# Industrial-Controller_Fan.net
KiCad netlist of a schematic drawn in Altium Designer
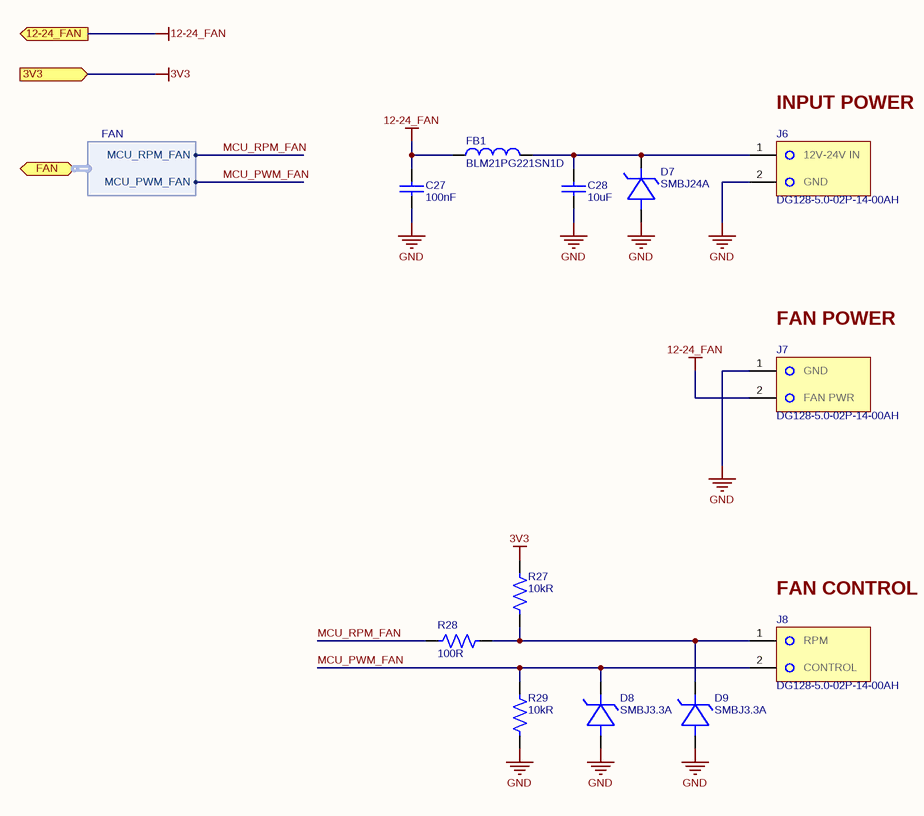
[diagram p0: Industrial-Controller_Fan.SchDoc]

(export (version "E")
  (design (tool "Eeschema 10.0.6"))
  (components
    (comp (ref "C27")
      (value "100nF")
      (footprint "CAP_0603")
      (description "CAP CER 0.1UF 50V X7R 0603")
      (fields (field (name "TOLERANCE") "10%"))
      (libsource (lib "Industrial-Controller") (part "CL10B104KB8NNNL"))
    )
    (comp (ref "C28")
      (value "10uF")
      (footprint "CAP_1210")
      (description "CAP CER 10UF 50V X7R 1210")
      (fields (field (name "TOLERANCE") "10%"))
      (libsource (lib "Industrial-Controller") (part "CL32B106KBJNNWE"))
    )
    (comp (ref "D7")
      (value "SMBJ24A")
      (footprint "SMB")
      (description "TVS DIODE 24VWM 38.9VC SMB")
      (libsource (lib "Industrial-Controller") (part "SMBJ24A"))
    )
    (comp (ref "D8")
      (value "SMBJ3.3A")
      (footprint "SMB")
      (description "TVS DIODE 3.3VWM 4.1VC SMB")
      (libsource (lib "Industrial-Controller") (part "SMBJ3.3A"))
    )
    (comp (ref "D9")
      (value "SMBJ3.3A")
      (footprint "SMB")
      (description "TVS DIODE 3.3VWM 4.1VC SMB")
      (libsource (lib "Industrial-Controller") (part "SMBJ3.3A"))
    )
    (comp (ref "FB1")
      (value "BLM21PG221SN1D")
      (footprint "L0805")
      (description "FERRITE BEAD 220 OHM 0805 1LN")
      (fields (field (name "TOLERANCE") "25%"))
      (libsource (lib "Industrial-Controller") (part "BLM21PG221SN1D"))
    )
    (comp (ref "J6")
      (value "DG128-5.0-02P-14-00AH")
      (footprint "DG128-5.0-02P-14")
      (description "TERM BLK 2P TOP ENTRY 5MM SMD")
      (libsource (lib "Industrial-Controller") (part "DG128-5.0-02P-14"))
    )
    (comp (ref "J7")
      (value "DG128-5.0-02P-14-00AH")
      (footprint "DG128-5.0-02P-14")
      (description "TERM BLK 2P TOP ENTRY 5MM SMD")
      (libsource (lib "Industrial-Controller") (part "DG128-5.0-02P-14"))
    )
    (comp (ref "J8")
      (value "DG128-5.0-02P-14-00AH")
      (footprint "DG128-5.0-02P-14")
      (description "TERM BLK 2P TOP ENTRY 5MM SMD")
      (libsource (lib "Industrial-Controller") (part "DG128-5.0-02P-14"))
    )
    (comp (ref "R27")
      (value "10kR")
      (footprint "RES_0603")
      (description "RES 10K OHM 1% 1/10W 0603")
      (fields (field (name "TOLERANCE") "1%"))
      (libsource (lib "Industrial-Controller") (part "RC0603FR-0710KL"))
    )
    (comp (ref "R28")
      (value "100R")
      (footprint "RES_0603")
      (description "RES 100 OHM 1% 1/10W 0603")
      (fields (field (name "TOLERANCE") "1%"))
      (libsource (lib "Industrial-Controller") (part "RC0603FR-07100RL"))
    )
    (comp (ref "R29")
      (value "10kR")
      (footprint "RES_0603")
      (description "RES 10K OHM 1% 1/10W 0603")
      (fields (field (name "TOLERANCE") "1%"))
      (libsource (lib "Industrial-Controller") (part "RC0603FR-0710KL"))
    )
  )
  (nets
    (net (code "2") (name "/MCU_PWM_FAN") (class "Default")
      (node (ref "D8") (pin "1") (pinfunction "C_1") (pintype "passive"))
      (node (ref "J8") (pin "2") (pinfunction "2_2") (pintype "passive"))
      (node (ref "R29") (pin "1") (pinfunction "1_1") (pintype "passive"))
    )
    (net (code "3") (name "/MCU_RPM_FAN") (class "Default")
      (node (ref "R28") (pin "2") (pinfunction "2_2") (pintype "passive"))
    )
    (net (code "5") (name "3V3") (class "Default")
      (node (ref "R27") (pin "1") (pinfunction "1_1") (pintype "passive"))
    )
    (net (code "6") (name "12-24_FAN") (class "Default")
      (node (ref "C27") (pin "1") (pinfunction "1_1") (pintype "passive"))
      (node (ref "FB1") (pin "1") (pinfunction "1_1") (pintype "passive"))
      (node (ref "J7") (pin "2") (pinfunction "2_2") (pintype "passive"))
    )
    (net (code "7") (name "GND") (class "Default")
      (node (ref "C27") (pin "2") (pinfunction "2_2") (pintype "passive"))
      (node (ref "C28") (pin "1") (pinfunction "1_1") (pintype "passive"))
      (node (ref "D7") (pin "2") (pinfunction "A_2") (pintype "passive"))
      (node (ref "D8") (pin "2") (pinfunction "A_2") (pintype "passive"))
      (node (ref "D9") (pin "2") (pinfunction "A_2") (pintype "passive"))
      (node (ref "J6") (pin "2") (pinfunction "2_2") (pintype "passive"))
      (node (ref "J7") (pin "1") (pinfunction "1_1") (pintype "passive"))
      (node (ref "R29") (pin "2") (pinfunction "2_2") (pintype "passive"))
    )
    (net (code "8") (name "Net-(D7-C)") (class "Default")
      (node (ref "C28") (pin "2") (pinfunction "2_2") (pintype "passive"))
      (node (ref "D7") (pin "1") (pinfunction "C_1") (pintype "passive"))
      (node (ref "FB1") (pin "2") (pinfunction "2_2") (pintype "passive"))
      (node (ref "J6") (pin "1") (pinfunction "1_1") (pintype "passive"))
    )
    (net (code "9") (name "Net-(D9-C)") (class "Default")
      (node (ref "D9") (pin "1") (pinfunction "C_1") (pintype "passive"))
      (node (ref "J8") (pin "1") (pinfunction "1_1") (pintype "passive"))
      (node (ref "R27") (pin "2") (pinfunction "2_2") (pintype "passive"))
      (node (ref "R28") (pin "1") (pinfunction "1_1") (pintype "passive"))
    )
  )
)
